# design.net
KiCad netlist of a schematic drawn in Altium Designer
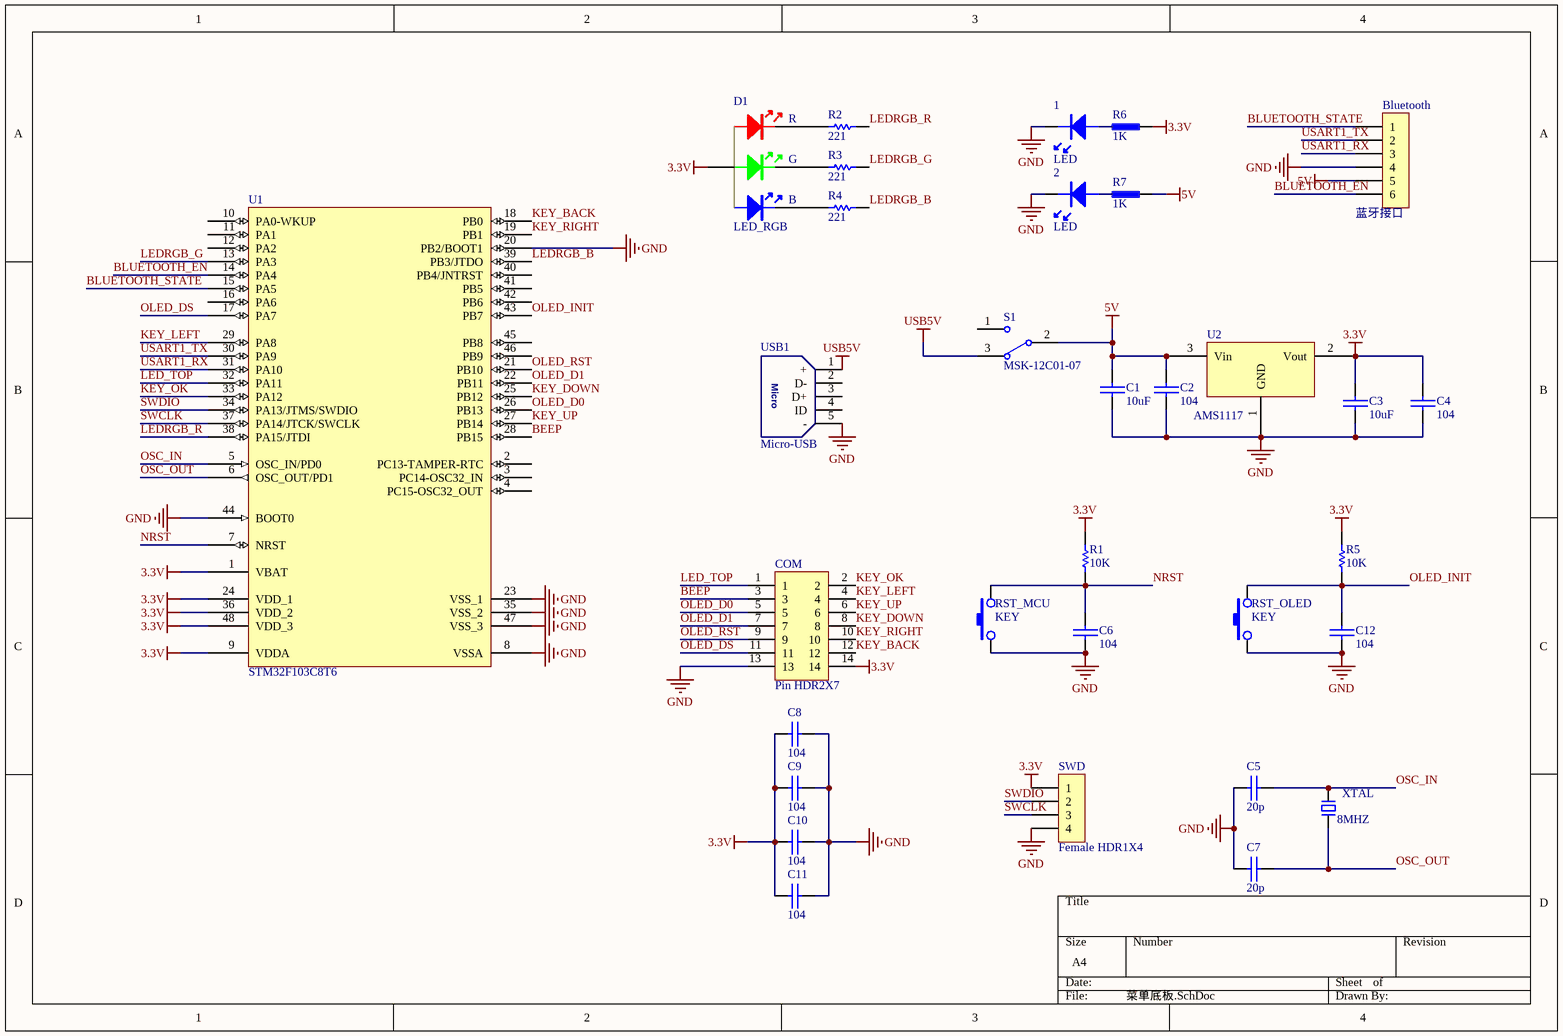
[diagram p0: 菜单底板.SchDoc]

(export (version "E")
  (design (tool "Eeschema 10.0.6"))
  (components
    (comp (ref "1") (value "LED") (footprint "LED-0805B") (libsource (lib "LED") (part "LED")))
    (comp (ref "2") (value "LED") (footprint "LED-0805B") (libsource (lib "LED") (part "LED")))
    (comp (ref "Bluetooth")
      (value "蓝牙接口")
      (footprint "Fe-HDR1X6/2.54-S")
      (libsource (lib "排母") (part "Female HDR1X6"))
    )
    (comp (ref "C1")
      (value "10uF")
      (footprint "0805C")
      (description "无极性电容")
      (libsource (lib "电容") (part "CAP"))
    )
    (comp (ref "C2")
      (value "104")
      (footprint "0805C")
      (description "无极性电容")
      (libsource (lib "电容") (part "CAP"))
    )
    (comp (ref "C3")
      (value "10uF")
      (footprint "0805C")
      (description "无极性电容")
      (libsource (lib "电容") (part "CAP"))
    )
    (comp (ref "C4")
      (value "104")
      (footprint "0805C")
      (description "无极性电容")
      (libsource (lib "电容") (part "CAP"))
    )
    (comp (ref "C5")
      (value "20p")
      (footprint "0805C")
      (description "无极性电容")
      (libsource (lib "电容") (part "CAP"))
    )
    (comp (ref "C6")
      (value "104")
      (footprint "0805C")
      (description "无极性电容")
      (libsource (lib "电容") (part "CAP"))
    )
    (comp (ref "C7")
      (value "20p")
      (footprint "0805C")
      (description "无极性电容")
      (libsource (lib "电容") (part "CAP"))
    )
    (comp (ref "C8")
      (value "104")
      (footprint "0805C")
      (description "无极性电容")
      (libsource (lib "电容") (part "CAP"))
    )
    (comp (ref "C9")
      (value "104")
      (footprint "0805C")
      (description "无极性电容")
      (libsource (lib "电容") (part "CAP"))
    )
    (comp (ref "C10")
      (value "104")
      (footprint "0805C")
      (description "无极性电容")
      (libsource (lib "电容") (part "CAP"))
    )
    (comp (ref "C11")
      (value "104")
      (footprint "0805C")
      (description "无极性电容")
      (libsource (lib "电容") (part "CAP"))
    )
    (comp (ref "C12")
      (value "104")
      (footprint "0805C")
      (description "无极性电容")
      (libsource (lib "电容") (part "CAP"))
    )
    (comp (ref "COM")
      (value "Pin HDR2X7")
      (footprint "Pin HDR2X7/2.54mm-S")
      (libsource (lib "排针") (part "Pin HDR2X7"))
    )
    (comp (ref "D1")
      (value "LED_RGB")
      (footprint "LED  3528SMD")
      (description "贴片0805， 深圳市追芯电子")
      (libsource (lib "LED") (part "LED_RGB"))
    )
    (comp (ref "R1") (value "10K") (footprint "0805R") (libsource (lib "电阻") (part "RES")))
    (comp (ref "R2") (value "221") (footprint "0805R") (libsource (lib "电阻") (part "RES")))
    (comp (ref "R3") (value "221") (footprint "0805R") (libsource (lib "电阻") (part "RES")))
    (comp (ref "R4") (value "221") (footprint "0805R") (libsource (lib "电阻") (part "RES")))
    (comp (ref "R5") (value "10K") (footprint "0805R") (libsource (lib "电阻") (part "RES")))
    (comp (ref "R6") (value "1K") (footprint "R 0805") (libsource (lib "常用原理图库") (part "RES")))
    (comp (ref "R7") (value "1K") (footprint "R 0805") (libsource (lib "常用原理图库") (part "RES")))
    (comp (ref "RST_MCU") (value "KEY") (footprint "DIP-6X6X6_C") (libsource (lib "轻触开关") (part "KEY")))
    (comp (ref "RST_OLED") (value "KEY") (footprint "DIP-6X6X6_C") (libsource (lib "轻触开关") (part "KEY")))
    (comp (ref "S1")
      (value "MSK-12C01-07")
      (footprint "MSK-12C01-07")
      (libsource (lib "电源开关") (part "MSK-12C01-07"))
    )
    (comp (ref "SWD")
      (value "Female HDR1X4")
      (footprint "Fe-HDR1X4/2.54-S")
      (libsource (lib "排母") (part "Female HDR1X4"))
    )
    (comp (ref "U1")
      (value "STM32F103C8T6")
      (footprint "LQFP48 7X7")
      (libsource (lib "STM32系列") (part "STM32F103C8T6"))
    )
    (comp (ref "U2")
      (value "AMS1117")
      (footprint "SOT223")
      (description "三端稳压芯片")
      (libsource (lib "电源芯片") (part "AMS1117"))
    )
    (comp (ref "USB1")
      (value "Micro-USB")
      (footprint "USB-MICRO_D")
      (libsource (lib "USB") (part "Micro-USB"))
    )
    (comp (ref "XTAL")
      (value "8MHZ")
      (footprint "OSC HC-49SMD")
      (description "2脚无源脚晶振")
      (libsource (lib "晶振") (part "XTAL-2P"))
    )
  )
  (nets
    (net (code "1") (name "/BEEP") (class "Default")
      (node (ref "COM") (pin "3") (pinfunction "3_3") (pintype "passive"))
      (node (ref "U1") (pin "28") (pinfunction "PB15_28") (pintype "bidirectional"))
    )
    (net (code "2") (name "/BLUETOOTH_EN") (class "Default")
      (node (ref "Bluetooth") (pin "6") (pinfunction "6_6") (pintype "passive"))
      (node (ref "U1") (pin "14") (pinfunction "PA4_14") (pintype "bidirectional"))
    )
    (net (code "3") (name "/BLUETOOTH_STATE") (class "Default")
      (node (ref "Bluetooth") (pin "1") (pinfunction "1_1") (pintype "passive"))
      (node (ref "U1") (pin "15") (pinfunction "PA5_15") (pintype "bidirectional"))
    )
    (net (code "4") (name "/KEY_BACK") (class "Default")
      (node (ref "COM") (pin "12") (pinfunction "12_12") (pintype "passive"))
      (node (ref "U1") (pin "18") (pinfunction "PB0_18") (pintype "bidirectional"))
    )
    (net (code "5") (name "/KEY_DOWN") (class "Default")
      (node (ref "COM") (pin "8") (pinfunction "8_8") (pintype "passive"))
      (node (ref "U1") (pin "25") (pinfunction "PB12_25") (pintype "bidirectional"))
    )
    (net (code "6") (name "/KEY_LEFT") (class "Default")
      (node (ref "COM") (pin "4") (pinfunction "4_4") (pintype "passive"))
      (node (ref "U1") (pin "29") (pinfunction "PA8_29") (pintype "bidirectional"))
    )
    (net (code "7") (name "/KEY_OK") (class "Default")
      (node (ref "COM") (pin "2") (pinfunction "2_2") (pintype "passive"))
      (node (ref "U1") (pin "33") (pinfunction "PA12_33") (pintype "bidirectional"))
    )
    (net (code "8") (name "/KEY_RIGHT") (class "Default")
      (node (ref "COM") (pin "10") (pinfunction "10_10") (pintype "passive"))
      (node (ref "U1") (pin "19") (pinfunction "PB1_19") (pintype "bidirectional"))
    )
    (net (code "9") (name "/KEY_UP") (class "Default")
      (node (ref "COM") (pin "6") (pinfunction "6_6") (pintype "passive"))
      (node (ref "U1") (pin "27") (pinfunction "PB14_27") (pintype "bidirectional"))
    )
    (net (code "10") (name "/LEDRGB_B") (class "Default")
      (node (ref "R4") (pin "1") (pinfunction "1_1") (pintype "passive"))
      (node (ref "U1") (pin "39") (pinfunction "PB3/JTDO_39") (pintype "bidirectional"))
    )
    (net (code "11") (name "/LEDRGB_G") (class "Default")
      (node (ref "R3") (pin "1") (pinfunction "1_1") (pintype "passive"))
      (node (ref "U1") (pin "13") (pinfunction "PA3_13") (pintype "bidirectional"))
    )
    (net (code "12") (name "/LEDRGB_R") (class "Default")
      (node (ref "R2") (pin "1") (pinfunction "1_1") (pintype "passive"))
      (node (ref "U1") (pin "38") (pinfunction "PA15/JTDI_38") (pintype "bidirectional"))
    )
    (net (code "13") (name "/LED_TOP") (class "Default")
      (node (ref "COM") (pin "1") (pinfunction "1_1") (pintype "passive"))
      (node (ref "U1") (pin "32") (pinfunction "PA11_32") (pintype "bidirectional"))
    )
    (net (code "14") (name "/NRST") (class "Default")
      (node (ref "C6") (pin "2") (pinfunction "2_2") (pintype "passive"))
      (node (ref "R1") (pin "1") (pinfunction "1_1") (pintype "passive"))
      (node (ref "RST_MCU") (pin "3") (pinfunction "3_3") (pintype "passive"))
      (node (ref "U1") (pin "7") (pinfunction "NRST_7") (pintype "bidirectional"))
    )
    (net (code "15") (name "/OLED_D0") (class "Default")
      (node (ref "COM") (pin "5") (pinfunction "5_5") (pintype "passive"))
      (node (ref "U1") (pin "26") (pinfunction "PB13_26") (pintype "bidirectional"))
    )
    (net (code "16") (name "/OLED_D1") (class "Default")
      (node (ref "COM") (pin "7") (pinfunction "7_7") (pintype "passive"))
      (node (ref "U1") (pin "22") (pinfunction "PB11_22") (pintype "bidirectional"))
    )
    (net (code "17") (name "/OLED_DS") (class "Default")
      (node (ref "COM") (pin "11") (pinfunction "11_11") (pintype "passive"))
      (node (ref "U1") (pin "17") (pinfunction "PA7_17") (pintype "bidirectional"))
    )
    (net (code "18") (name "/OLED_INIT") (class "Default")
      (node (ref "C12") (pin "2") (pinfunction "2_2") (pintype "passive"))
      (node (ref "R5") (pin "1") (pinfunction "1_1") (pintype "passive"))
      (node (ref "RST_OLED") (pin "3") (pinfunction "3_3") (pintype "passive"))
      (node (ref "U1") (pin "43") (pinfunction "PB7_43") (pintype "bidirectional"))
    )
    (net (code "19") (name "/OLED_RST") (class "Default")
      (node (ref "COM") (pin "9") (pinfunction "9_9") (pintype "passive"))
      (node (ref "U1") (pin "21") (pinfunction "PB10_21") (pintype "bidirectional"))
    )
    (net (code "20") (name "/OSC_IN") (class "Default")
      (node (ref "C5") (pin "2") (pinfunction "2_2") (pintype "passive"))
      (node (ref "U1") (pin "5") (pinfunction "OSC_IN/PD0_5") (pintype "input"))
      (node (ref "XTAL") (pin "2") (pinfunction "2_2") (pintype "passive"))
    )
    (net (code "21") (name "/OSC_OUT") (class "Default")
      (node (ref "C7") (pin "2") (pinfunction "2_2") (pintype "passive"))
      (node (ref "U1") (pin "6") (pinfunction "OSC_OUT/PD1_6") (pintype "output"))
      (node (ref "XTAL") (pin "1") (pinfunction "1_1") (pintype "passive"))
    )
    (net (code "22") (name "/SWCLK") (class "Default")
      (node (ref "SWD") (pin "3") (pinfunction "3_3") (pintype "passive"))
      (node (ref "U1") (pin "37") (pinfunction "PA14/JTCK/SWCLK_37") (pintype "bidirectional"))
    )
    (net (code "23") (name "/SWDIO") (class "Default")
      (node (ref "SWD") (pin "2") (pinfunction "2_2") (pintype "passive"))
      (node (ref "U1") (pin "34") (pinfunction "PA13/JTMS/SWDIO_34") (pintype "bidirectional"))
    )
    (net (code "24") (name "/USART1_RX") (class "Default")
      (node (ref "Bluetooth") (pin "3") (pinfunction "3_3") (pintype "passive"))
      (node (ref "U1") (pin "31") (pinfunction "PA10_31") (pintype "bidirectional"))
    )
    (net (code "25") (name "/USART1_TX") (class "Default")
      (node (ref "Bluetooth") (pin "2") (pinfunction "2_2") (pintype "passive"))
      (node (ref "U1") (pin "30") (pinfunction "PA9_30") (pintype "bidirectional"))
    )
    (net (code "26") (name "3.3V") (class "Default")
      (node (ref "C10") (pin "2") (pinfunction "2_2") (pintype "passive"))
      (node (ref "C11") (pin "2") (pinfunction "2_2") (pintype "passive"))
      (node (ref "C3") (pin "2") (pinfunction "2_2") (pintype "passive"))
      (node (ref "C4") (pin "2") (pinfunction "2_2") (pintype "passive"))
      (node (ref "C8") (pin "2") (pinfunction "2_2") (pintype "passive"))
      (node (ref "C9") (pin "2") (pinfunction "2_2") (pintype "passive"))
      (node (ref "COM") (pin "14") (pinfunction "14_14") (pintype "passive"))
      (node (ref "D1") (pin "3") (pinfunction "3_3") (pintype "passive"))
      (node (ref "R1") (pin "2") (pinfunction "2_2") (pintype "passive"))
      (node (ref "R5") (pin "2") (pinfunction "2_2") (pintype "passive"))
      (node (ref "R6") (pin "1") (pintype "passive"))
      (node (ref "SWD") (pin "1") (pinfunction "1_1") (pintype "passive"))
      (node (ref "U1") (pin "1") (pinfunction "VBAT_1") (pintype "power_in"))
      (node (ref "U1") (pin "24") (pinfunction "VDD_1_24") (pintype "power_in"))
      (node (ref "U1") (pin "36") (pinfunction "VDD_2_36") (pintype "power_in"))
      (node (ref "U1") (pin "48") (pinfunction "VDD_3_48") (pintype "power_in"))
      (node (ref "U1") (pin "9") (pinfunction "VDDA_9") (pintype "power_in"))
      (node (ref "U2") (pin "2") (pinfunction "Vout_2") (pintype "passive"))
    )
    (net (code "27") (name "5V") (class "Default")
      (node (ref "Bluetooth") (pin "5") (pinfunction "5_5") (pintype "passive"))
      (node (ref "C1") (pin "2") (pinfunction "2_2") (pintype "passive"))
      (node (ref "C2") (pin "2") (pinfunction "2_2") (pintype "passive"))
      (node (ref "R7") (pin "1") (pintype "passive"))
      (node (ref "S1") (pin "2") (pinfunction "2_2") (pintype "passive"))
      (node (ref "U2") (pin "3") (pinfunction "Vin_3") (pintype "passive"))
    )
    (net (code "28") (name "GND") (class "Default")
      (node (ref "1") (pin "K") (pinfunction "K_K") (pintype "passive"))
      (node (ref "2") (pin "K") (pinfunction "K_K") (pintype "passive"))
      (node (ref "Bluetooth") (pin "4") (pinfunction "4_4") (pintype "passive"))
      (node (ref "C1") (pin "1") (pinfunction "1_1") (pintype "passive"))
      (node (ref "C10") (pin "1") (pinfunction "1_1") (pintype "passive"))
      (node (ref "C11") (pin "1") (pinfunction "1_1") (pintype "passive"))
      (node (ref "C12") (pin "1") (pinfunction "1_1") (pintype "passive"))
      (node (ref "C2") (pin "1") (pinfunction "1_1") (pintype "passive"))
      (node (ref "C3") (pin "1") (pinfunction "1_1") (pintype "passive"))
      (node (ref "C4") (pin "1") (pinfunction "1_1") (pintype "passive"))
      (node (ref "C5") (pin "1") (pinfunction "1_1") (pintype "passive"))
      (node (ref "C6") (pin "1") (pinfunction "1_1") (pintype "passive"))
      (node (ref "C7") (pin "1") (pinfunction "1_1") (pintype "passive"))
      (node (ref "C8") (pin "1") (pinfunction "1_1") (pintype "passive"))
      (node (ref "C9") (pin "1") (pinfunction "1_1") (pintype "passive"))
      (node (ref "COM") (pin "13") (pinfunction "13_13") (pintype "passive"))
      (node (ref "RST_MCU") (pin "1") (pinfunction "1_1") (pintype "passive"))
      (node (ref "RST_OLED") (pin "1") (pinfunction "1_1") (pintype "passive"))
      (node (ref "SWD") (pin "4") (pinfunction "4_4") (pintype "passive"))
      (node (ref "U1") (pin "20") (pinfunction "PB2/BOOT1_20") (pintype "bidirectional"))
      (node (ref "U1") (pin "23") (pinfunction "VSS_1_23") (pintype "power_in"))
      (node (ref "U1") (pin "35") (pinfunction "VSS_2_35") (pintype "power_in"))
      (node (ref "U1") (pin "44") (pinfunction "BOOT0_44") (pintype "input"))
      (node (ref "U1") (pin "47") (pinfunction "VSS_3_47") (pintype "power_in"))
      (node (ref "U1") (pin "8") (pinfunction "VSSA_8") (pintype "power_in"))
      (node (ref "U2") (pin "1") (pinfunction "GND_1") (pintype "passive"))
      (node (ref "USB1") (pin "5") (pinfunction "-_5") (pintype "passive"))
    )
    (net (code "29") (name "Net-(1-PadA)") (class "Default")
      (node (ref "1") (pin "A") (pinfunction "A_A") (pintype "passive"))
      (node (ref "R6") (pin "2") (pintype "passive"))
    )
    (net (code "30") (name "Net-(2-PadA)") (class "Default")
      (node (ref "2") (pin "A") (pinfunction "A_A") (pintype "passive"))
      (node (ref "R7") (pin "2") (pintype "passive"))
    )
    (net (code "31") (name "Net-(D1-Pad1)") (class "Default")
      (node (ref "D1") (pin "1") (pinfunction "1_1") (pintype "passive"))
      (node (ref "R2") (pin "2") (pinfunction "2_2") (pintype "passive"))
    )
    (net (code "32") (name "Net-(D1-Pad2)") (class "Default")
      (node (ref "D1") (pin "2") (pinfunction "2_2") (pintype "passive"))
      (node (ref "R3") (pin "2") (pinfunction "2_2") (pintype "passive"))
    )
    (net (code "33") (name "Net-(D1-Pad4)") (class "Default")
      (node (ref "D1") (pin "4") (pinfunction "4_4") (pintype "passive"))
      (node (ref "R4") (pin "2") (pinfunction "2_2") (pintype "passive"))
    )
    (net (code "34") (name "USB5V") (class "Default")
      (node (ref "S1") (pin "3") (pinfunction "3_3") (pintype "passive"))
      (node (ref "USB1") (pin "1") (pinfunction "+_1") (pintype "passive"))
    )
    (net (code "35") (name "unconnected-(S1-Pad1)") (class "Default")
      (node (ref "S1") (pin "1") (pinfunction "1_1") (pintype "passive"))
    )
    (net (code "36") (name "unconnected-(U1-PA0-WKUP-Pad10)") (class "Default")
      (node (ref "U1") (pin "10") (pinfunction "PA0-WKUP_10") (pintype "bidirectional"))
    )
    (net (code "37") (name "unconnected-(U1-PA1-Pad11)") (class "Default")
      (node (ref "U1") (pin "11") (pinfunction "PA1_11") (pintype "bidirectional"))
    )
    (net (code "38") (name "unconnected-(U1-PA2-Pad12)") (class "Default")
      (node (ref "U1") (pin "12") (pinfunction "PA2_12") (pintype "bidirectional"))
    )
    (net (code "39") (name "unconnected-(U1-PA6-Pad16)") (class "Default")
      (node (ref "U1") (pin "16") (pinfunction "PA6_16") (pintype "bidirectional"))
    )
    (net (code "40") (name "unconnected-(U1-PB4{slash}JNTRST-Pad40)") (class "Default")
      (node (ref "U1") (pin "40") (pinfunction "PB4/JNTRST_40") (pintype "bidirectional"))
    )
    (net (code "41") (name "unconnected-(U1-PB5-Pad41)") (class "Default")
      (node (ref "U1") (pin "41") (pinfunction "PB5_41") (pintype "bidirectional"))
    )
    (net (code "42") (name "unconnected-(U1-PB6-Pad42)") (class "Default")
      (node (ref "U1") (pin "42") (pinfunction "PB6_42") (pintype "bidirectional"))
    )
    (net (code "43") (name "unconnected-(U1-PB8-Pad45)") (class "Default")
      (node (ref "U1") (pin "45") (pinfunction "PB8_45") (pintype "bidirectional"))
    )
    (net (code "44") (name "unconnected-(U1-PB9-Pad46)") (class "Default")
      (node (ref "U1") (pin "46") (pinfunction "PB9_46") (pintype "bidirectional"))
    )
    (net (code "45") (name "unconnected-(U1-PC13-TAMPER-RTC-Pad2)") (class "Default")
      (node (ref "U1") (pin "2") (pinfunction "PC13-TAMPER-RTC_2") (pintype "bidirectional"))
    )
    (net (code "46") (name "unconnected-(U1-PC14-OSC32_IN-Pad3)") (class "Default")
      (node (ref "U1") (pin "3") (pinfunction "PC14-OSC32_IN_3") (pintype "bidirectional"))
    )
    (net (code "47") (name "unconnected-(U1-PC15-OSC32_OUT-Pad4)") (class "Default")
      (node (ref "U1") (pin "4") (pinfunction "PC15-OSC32_OUT_4") (pintype "bidirectional"))
    )
    (net (code "48") (name "unconnected-(USB1-D+-Pad3)") (class "Default")
      (node (ref "USB1") (pin "3") (pinfunction "D+_3") (pintype "passive"))
    )
    (net (code "49") (name "unconnected-(USB1-D--Pad2)") (class "Default")
      (node (ref "USB1") (pin "2") (pinfunction "D-_2") (pintype "passive"))
    )
    (net (code "50") (name "unconnected-(USB1-ID-Pad4)") (class "Default")
      (node (ref "USB1") (pin "4") (pinfunction "ID_4") (pintype "passive"))
    )
  )
)
